# Maxim_7219_LED_display_Adafruit_0_56_7_s.net
KiCad netlist of a schematic drawn in EAGLE
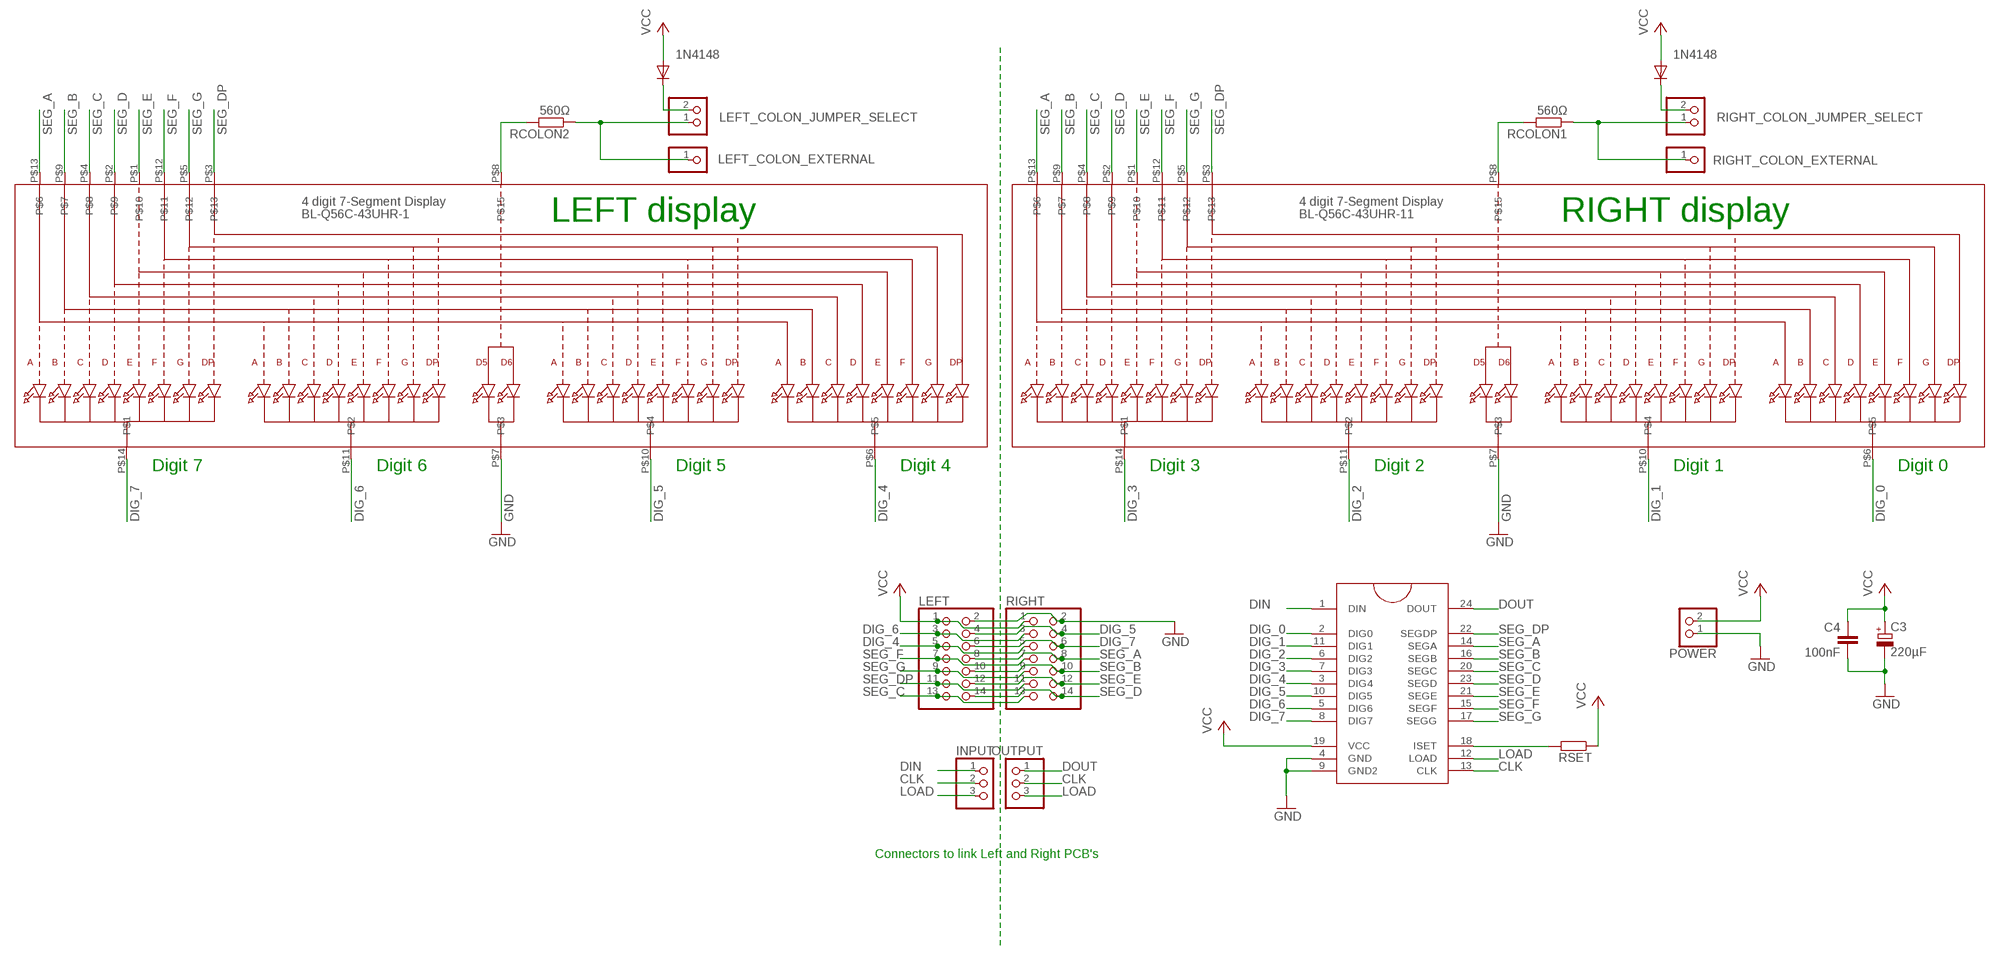
[diagram p0: schematic, sheet 1]

(export (version "E")
  (design (tool "Eeschema 10.0.6"))
  (components
    (comp (ref "BL-Q56C-43UHR-1")
      (value "4 digit 7-Segment Display")
      (footprint "eagle-import:SEGMENT-BL-Q56C43")
      (libsource (lib "eagle-import") (part "DISP_SEGMENT_4DIGIT_BL-Q56C43"))
    )
    (comp (ref "BL-Q56C-43UHR-11")
      (value "4 digit 7-Segment Display")
      (footprint "eagle-import:SEGMENT-BL-Q56C43")
      (libsource (lib "eagle-import") (part "DISP_SEGMENT_4DIGIT_BL-Q56C43"))
    )
    (comp (ref "C3")
      (value "220µF")
      (footprint "eagle-import:E5-10,5")
      (libsource (lib "eagle-import") (part "CPOL-EUE5-10.5"))
    )
    (comp (ref "C4")
      (value "100nF")
      (footprint "eagle-import:C050-025X075")
      (libsource (lib "eagle-import") (part "C-EU050-025X075"))
    )
    (comp (ref "D2")
      (value "1N4148")
      (footprint "eagle-import:DO35-7")
      (libsource (lib "eagle-import") (part "1N4148DO35-7"))
    )
    (comp (ref "D3")
      (value "1N4148")
      (footprint "eagle-import:DO35-7")
      (libsource (lib "eagle-import") (part "1N4148DO35-7"))
    )
    (comp (ref "INPUT")
      (value "PINHD-1X3")
      (footprint "eagle-import:1X03")
      (libsource (lib "eagle-import") (part "PINHD-1X3"))
    )
    (comp (ref "LEFT")
      (value "PINHD-2X7")
      (footprint "eagle-import:2X07")
      (libsource (lib "eagle-import") (part "PINHD-2X7"))
    )
    (comp (ref "LEFT_COLON_EXTERNAL")
      (value "M01SMDNS")
      (footprint "eagle-import:1X01")
      (libsource (lib "eagle-import") (part "PINHD-1X1"))
    )
    (comp (ref "LEFT_COLON_JUMPER_SELECT")
      (value "PINHD-1X2")
      (footprint "eagle-import:1X02")
      (libsource (lib "eagle-import") (part "PINHD-1X2"))
    )
    (comp (ref "OUTPUT")
      (value "PINHD-1X3")
      (footprint "eagle-import:1X03")
      (libsource (lib "eagle-import") (part "PINHD-1X3"))
    )
    (comp (ref "POWER")
      (value "PINHD-1X2")
      (footprint "eagle-import:1X02")
      (libsource (lib "eagle-import") (part "PINHD-1X2"))
    )
    (comp (ref "RCOLON1")
      (value "560Ω")
      (footprint "eagle-import:0207_10")
      (libsource (lib "eagle-import") (part "R-EU_0207/10"))
    )
    (comp (ref "RCOLON2")
      (value "560Ω")
      (footprint "eagle-import:0207_10")
      (libsource (lib "eagle-import") (part "R-EU_0207/10"))
    )
    (comp (ref "RIGHT")
      (value "PINHD-2X7")
      (footprint "eagle-import:2X07")
      (libsource (lib "eagle-import") (part "PINHD-2X7"))
    )
    (comp (ref "RIGHT_COLON_EXTERNAL")
      (value "PINHD-1X1")
      (footprint "eagle-import:1X01")
      (libsource (lib "eagle-import") (part "PINHD-1X1"))
    )
    (comp (ref "RIGHT_COLON_JUMPER_SELECT")
      (value "PINHD-1X2")
      (footprint "eagle-import:1X02")
      (libsource (lib "eagle-import") (part "PINHD-1X2"))
    )
    (comp (ref "RSET")
      (value "R-EU_0207/2V")
      (footprint "eagle-import:0207_2V")
      (libsource (lib "eagle-import") (part "R-EU_0207/2V"))
    )
    (comp (ref "U$3")
      (value "MAX7219DIP")
      (footprint "eagle-import:DIL24")
      (libsource (lib "eagle-import") (part "MAX7219DIP"))
    )
  )
  (nets
    (net (code "1") (name "/CLK") (class "Default")
      (node (ref "INPUT") (pin "2") (pinfunction "2_2") (pintype "passive"))
      (node (ref "OUTPUT") (pin "2") (pinfunction "2_2") (pintype "passive"))
      (node (ref "U$3") (pin "13") (pinfunction "CLK_13") (pintype "bidirectional"))
    )
    (net (code "2") (name "/DIG_0") (class "Default")
      (node (ref "BL-Q56C-43UHR-11") (pin "P$6") (pinfunction "P$5_P$6") (pintype "bidirectional"))
      (node (ref "U$3") (pin "2") (pinfunction "DIG0_2") (pintype "bidirectional"))
    )
    (net (code "3") (name "/DIG_1") (class "Default")
      (node (ref "BL-Q56C-43UHR-11") (pin "P$10") (pinfunction "P$4_P$10") (pintype "bidirectional"))
      (node (ref "U$3") (pin "11") (pinfunction "DIG1_11") (pintype "bidirectional"))
    )
    (net (code "4") (name "/DIG_2") (class "Default")
      (node (ref "BL-Q56C-43UHR-11") (pin "P$11") (pinfunction "P$2_P$11") (pintype "bidirectional"))
      (node (ref "U$3") (pin "6") (pinfunction "DIG2_6") (pintype "bidirectional"))
    )
    (net (code "5") (name "/DIG_3") (class "Default")
      (node (ref "BL-Q56C-43UHR-11") (pin "P$14") (pinfunction "P$1_P$14") (pintype "bidirectional"))
      (node (ref "U$3") (pin "7") (pinfunction "DIG3_7") (pintype "bidirectional"))
    )
    (net (code "6") (name "/DIG_4") (class "Default")
      (node (ref "BL-Q56C-43UHR-1") (pin "P$6") (pinfunction "P$5_P$6") (pintype "bidirectional"))
      (node (ref "LEFT") (pin "5") (pinfunction "5_5") (pintype "passive"))
      (node (ref "RIGHT") (pin "5") (pinfunction "5_5") (pintype "passive"))
      (node (ref "U$3") (pin "3") (pinfunction "DIG4_3") (pintype "bidirectional"))
    )
    (net (code "7") (name "/DIG_5") (class "Default")
      (node (ref "BL-Q56C-43UHR-1") (pin "P$10") (pinfunction "P$4_P$10") (pintype "bidirectional"))
      (node (ref "LEFT") (pin "4") (pinfunction "4_4") (pintype "passive"))
      (node (ref "RIGHT") (pin "4") (pinfunction "4_4") (pintype "passive"))
      (node (ref "U$3") (pin "10") (pinfunction "DIG5_10") (pintype "bidirectional"))
    )
    (net (code "8") (name "/DIG_6") (class "Default")
      (node (ref "BL-Q56C-43UHR-1") (pin "P$11") (pinfunction "P$2_P$11") (pintype "bidirectional"))
      (node (ref "LEFT") (pin "3") (pinfunction "3_3") (pintype "passive"))
      (node (ref "RIGHT") (pin "3") (pinfunction "3_3") (pintype "passive"))
      (node (ref "U$3") (pin "5") (pinfunction "DIG6_5") (pintype "bidirectional"))
    )
    (net (code "9") (name "/DIG_7") (class "Default")
      (node (ref "BL-Q56C-43UHR-1") (pin "P$14") (pinfunction "P$1_P$14") (pintype "bidirectional"))
      (node (ref "LEFT") (pin "6") (pinfunction "6_6") (pintype "passive"))
      (node (ref "RIGHT") (pin "6") (pinfunction "6_6") (pintype "passive"))
      (node (ref "U$3") (pin "8") (pinfunction "DIG7_8") (pintype "bidirectional"))
    )
    (net (code "10") (name "/DIN") (class "Default")
      (node (ref "INPUT") (pin "1") (pinfunction "1_1") (pintype "passive"))
      (node (ref "U$3") (pin "1") (pinfunction "DIN_1") (pintype "bidirectional"))
    )
    (net (code "11") (name "/DOUT") (class "Default")
      (node (ref "OUTPUT") (pin "1") (pinfunction "1_1") (pintype "passive"))
      (node (ref "U$3") (pin "24") (pinfunction "DOUT_24") (pintype "bidirectional"))
    )
    (net (code "12") (name "/LOAD") (class "Default")
      (node (ref "INPUT") (pin "3") (pinfunction "3_3") (pintype "passive"))
      (node (ref "OUTPUT") (pin "3") (pinfunction "3_3") (pintype "passive"))
      (node (ref "U$3") (pin "12") (pinfunction "LOAD_12") (pintype "bidirectional"))
    )
    (net (code "13") (name "/SEG_A") (class "Default")
      (node (ref "BL-Q56C-43UHR-1") (pin "P$13") (pinfunction "P$6_P$13") (pintype "bidirectional"))
      (node (ref "BL-Q56C-43UHR-11") (pin "P$13") (pinfunction "P$6_P$13") (pintype "bidirectional"))
      (node (ref "LEFT") (pin "8") (pinfunction "8_8") (pintype "passive"))
      (node (ref "RIGHT") (pin "8") (pinfunction "8_8") (pintype "passive"))
      (node (ref "U$3") (pin "14") (pinfunction "SEGA_14") (pintype "bidirectional"))
    )
    (net (code "14") (name "/SEG_B") (class "Default")
      (node (ref "BL-Q56C-43UHR-1") (pin "P$9") (pinfunction "P$7_P$9") (pintype "bidirectional"))
      (node (ref "BL-Q56C-43UHR-11") (pin "P$9") (pinfunction "P$7_P$9") (pintype "bidirectional"))
      (node (ref "LEFT") (pin "10") (pinfunction "10_10") (pintype "passive"))
      (node (ref "RIGHT") (pin "10") (pinfunction "10_10") (pintype "passive"))
      (node (ref "U$3") (pin "16") (pinfunction "SEGB_16") (pintype "bidirectional"))
    )
    (net (code "15") (name "/SEG_C") (class "Default")
      (node (ref "BL-Q56C-43UHR-1") (pin "P$4") (pinfunction "P$8_P$4") (pintype "bidirectional"))
      (node (ref "BL-Q56C-43UHR-11") (pin "P$4") (pinfunction "P$8_P$4") (pintype "bidirectional"))
      (node (ref "LEFT") (pin "13") (pinfunction "13_13") (pintype "passive"))
      (node (ref "RIGHT") (pin "13") (pinfunction "13_13") (pintype "passive"))
      (node (ref "U$3") (pin "20") (pinfunction "SEGC_20") (pintype "bidirectional"))
    )
    (net (code "16") (name "/SEG_D") (class "Default")
      (node (ref "BL-Q56C-43UHR-1") (pin "P$2") (pinfunction "P$9_P$2") (pintype "bidirectional"))
      (node (ref "BL-Q56C-43UHR-11") (pin "P$2") (pinfunction "P$9_P$2") (pintype "bidirectional"))
      (node (ref "LEFT") (pin "14") (pinfunction "14_14") (pintype "passive"))
      (node (ref "RIGHT") (pin "14") (pinfunction "14_14") (pintype "passive"))
      (node (ref "U$3") (pin "23") (pinfunction "SEGD_23") (pintype "bidirectional"))
    )
    (net (code "17") (name "/SEG_DP") (class "Default")
      (node (ref "BL-Q56C-43UHR-1") (pin "P$3") (pinfunction "P$13_P$3") (pintype "bidirectional"))
      (node (ref "BL-Q56C-43UHR-11") (pin "P$3") (pinfunction "P$13_P$3") (pintype "bidirectional"))
      (node (ref "LEFT") (pin "11") (pinfunction "11_11") (pintype "passive"))
      (node (ref "RIGHT") (pin "11") (pinfunction "11_11") (pintype "passive"))
      (node (ref "U$3") (pin "22") (pinfunction "SEGDP_22") (pintype "bidirectional"))
    )
    (net (code "18") (name "/SEG_E") (class "Default")
      (node (ref "BL-Q56C-43UHR-1") (pin "P$1") (pinfunction "P$10_P$1") (pintype "bidirectional"))
      (node (ref "BL-Q56C-43UHR-11") (pin "P$1") (pinfunction "P$10_P$1") (pintype "bidirectional"))
      (node (ref "LEFT") (pin "12") (pinfunction "12_12") (pintype "passive"))
      (node (ref "RIGHT") (pin "12") (pinfunction "12_12") (pintype "passive"))
      (node (ref "U$3") (pin "21") (pinfunction "SEGE_21") (pintype "bidirectional"))
    )
    (net (code "19") (name "/SEG_F") (class "Default")
      (node (ref "BL-Q56C-43UHR-1") (pin "P$12") (pinfunction "P$11_P$12") (pintype "bidirectional"))
      (node (ref "BL-Q56C-43UHR-11") (pin "P$12") (pinfunction "P$11_P$12") (pintype "bidirectional"))
      (node (ref "LEFT") (pin "7") (pinfunction "7_7") (pintype "passive"))
      (node (ref "RIGHT") (pin "7") (pinfunction "7_7") (pintype "passive"))
      (node (ref "U$3") (pin "15") (pinfunction "SEGF_15") (pintype "bidirectional"))
    )
    (net (code "20") (name "/SEG_G") (class "Default")
      (node (ref "BL-Q56C-43UHR-1") (pin "P$5") (pinfunction "P$12_P$5") (pintype "bidirectional"))
      (node (ref "BL-Q56C-43UHR-11") (pin "P$5") (pinfunction "P$12_P$5") (pintype "bidirectional"))
      (node (ref "LEFT") (pin "9") (pinfunction "9_9") (pintype "passive"))
      (node (ref "RIGHT") (pin "9") (pinfunction "9_9") (pintype "passive"))
      (node (ref "U$3") (pin "17") (pinfunction "SEGG_17") (pintype "bidirectional"))
    )
    (net (code "21") (name "GND") (class "Default")
      (node (ref "BL-Q56C-43UHR-1") (pin "P$7") (pinfunction "P$3_P$7") (pintype "bidirectional"))
      (node (ref "BL-Q56C-43UHR-11") (pin "P$7") (pinfunction "P$3_P$7") (pintype "bidirectional"))
      (node (ref "C3") (pin "-") (pinfunction "-_-") (pintype "passive"))
      (node (ref "C4") (pin "2") (pinfunction "2_2") (pintype "passive"))
      (node (ref "LEFT") (pin "2") (pinfunction "2_2") (pintype "passive"))
      (node (ref "POWER") (pin "1") (pinfunction "1_1") (pintype "passive"))
      (node (ref "RIGHT") (pin "2") (pinfunction "2_2") (pintype "passive"))
      (node (ref "U$3") (pin "4") (pinfunction "GND_4") (pintype "bidirectional"))
      (node (ref "U$3") (pin "9") (pinfunction "GND2_9") (pintype "bidirectional"))
    )
    (net (code "22") (name "Net-(BL-Q56C-43UHR-1-P$15)") (class "Default")
      (node (ref "BL-Q56C-43UHR-1") (pin "P$8") (pinfunction "P$15_P$8") (pintype "bidirectional"))
      (node (ref "RCOLON2") (pin "2") (pinfunction "2_2") (pintype "passive"))
    )
    (net (code "23") (name "Net-(BL-Q56C-43UHR-11-P$15)") (class "Default")
      (node (ref "BL-Q56C-43UHR-11") (pin "P$8") (pinfunction "P$15_P$8") (pintype "bidirectional"))
      (node (ref "RCOLON1") (pin "2") (pinfunction "2_2") (pintype "passive"))
    )
    (net (code "24") (name "Net-(D2-PadC)") (class "Default")
      (node (ref "D2") (pin "C") (pinfunction "C_C") (pintype "passive"))
      (node (ref "LEFT_COLON_JUMPER_SELECT") (pin "2") (pinfunction "2_2") (pintype "passive"))
    )
    (net (code "25") (name "Net-(D3-PadC)") (class "Default")
      (node (ref "D3") (pin "C") (pinfunction "C_C") (pintype "passive"))
      (node (ref "RIGHT_COLON_JUMPER_SELECT") (pin "2") (pinfunction "2_2") (pintype "passive"))
    )
    (net (code "26") (name "Net-(LEFT_COLON_EXTERNAL-Pad1)") (class "Default")
      (node (ref "LEFT_COLON_EXTERNAL") (pin "1") (pinfunction "1_1") (pintype "passive"))
      (node (ref "LEFT_COLON_JUMPER_SELECT") (pin "1") (pinfunction "1_1") (pintype "passive"))
      (node (ref "RCOLON2") (pin "1") (pinfunction "1_1") (pintype "passive"))
    )
    (net (code "27") (name "Net-(RCOLON1-Pad1)") (class "Default")
      (node (ref "RCOLON1") (pin "1") (pinfunction "1_1") (pintype "passive"))
      (node (ref "RIGHT_COLON_EXTERNAL") (pin "1") (pinfunction "1_1") (pintype "passive"))
      (node (ref "RIGHT_COLON_JUMPER_SELECT") (pin "1") (pinfunction "1_1") (pintype "passive"))
    )
    (net (code "28") (name "Net-(U$3-ISET)") (class "Default")
      (node (ref "RSET") (pin "2") (pinfunction "2_2") (pintype "passive"))
      (node (ref "U$3") (pin "18") (pinfunction "ISET_18") (pintype "bidirectional"))
    )
    (net (code "29") (name "VCC") (class "Default")
      (node (ref "C3") (pin "+") (pinfunction "+_+") (pintype "passive"))
      (node (ref "C4") (pin "1") (pinfunction "1_1") (pintype "passive"))
      (node (ref "D2") (pin "A") (pinfunction "A_A") (pintype "passive"))
      (node (ref "D3") (pin "A") (pinfunction "A_A") (pintype "passive"))
      (node (ref "LEFT") (pin "1") (pinfunction "1_1") (pintype "passive"))
      (node (ref "POWER") (pin "2") (pinfunction "2_2") (pintype "passive"))
      (node (ref "RIGHT") (pin "1") (pinfunction "1_1") (pintype "passive"))
      (node (ref "RSET") (pin "1") (pinfunction "1_1") (pintype "passive"))
      (node (ref "U$3") (pin "19") (pinfunction "VCC_19") (pintype "bidirectional"))
    )
  )
)
